# plooter_2.net
KiCad netlist of a schematic drawn in EAGLE
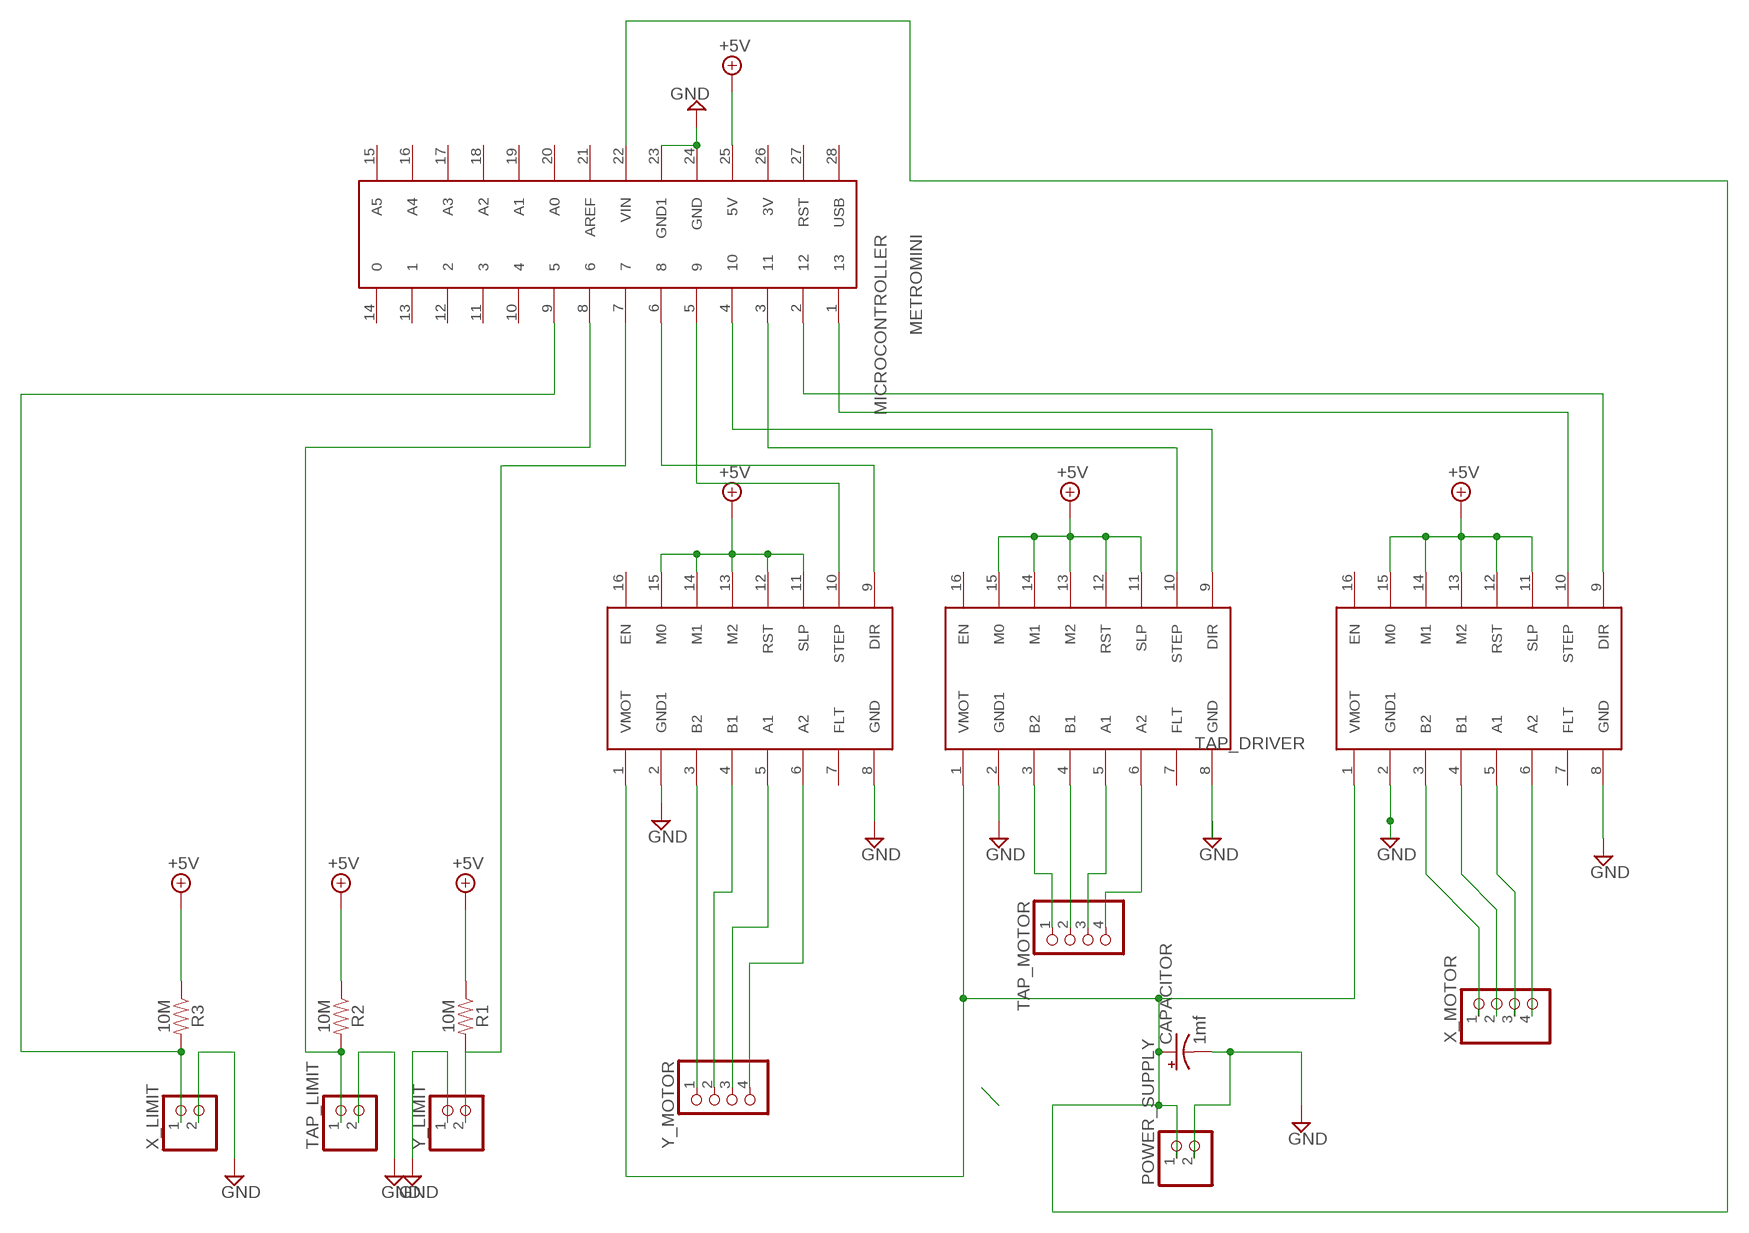
[diagram p0: schematic, sheet 1]

(export (version "E")
  (design (tool "Eeschema 10.0.6"))
  (components
    (comp (ref "CAPACITOR")
      (value "1mf")
      (footprint "eagle-import:CPOL-RADIAL-5MM-10MM-KIT")
      (libsource (lib "eagle-import") (part "1000UF-RADIAL-5MM-35V-20%-KIT"))
    )
    (comp (ref "MICROCONTROLLER")
      (value "METROMINI")
      (footprint "eagle-import:METROMINI")
      (libsource (lib "eagle-import") (part "METROMINI"))
    )
    (comp (ref "POWER_SUPPLY")
      (value "PINHD-1X2")
      (footprint "eagle-import:1X02")
      (libsource (lib "eagle-import") (part "PINHD-1X2"))
    )
    (comp (ref "R1")
      (value "10M")
      (footprint "eagle-import:AXIAL-0.3")
      (libsource (lib "eagle-import") (part "10MOHM-HORIZ-1/4W-5%"))
    )
    (comp (ref "R2")
      (value "10M")
      (footprint "eagle-import:AXIAL-0.3")
      (libsource (lib "eagle-import") (part "10MOHM-HORIZ-1/4W-5%"))
    )
    (comp (ref "R3")
      (value "10M")
      (footprint "eagle-import:AXIAL-0.3")
      (libsource (lib "eagle-import") (part "10MOHM-HORIZ-1/4W-5%"))
    )
    (comp (ref "TAP_DRIVER")
      (value "DRV8825")
      (footprint "eagle-import:DRV8825")
      (libsource (lib "eagle-import") (part "DRV8825"))
    )
    (comp (ref "TAP_LIMIT")
      (value "PINHD-1X2")
      (footprint "eagle-import:1X02")
      (libsource (lib "eagle-import") (part "PINHD-1X2"))
    )
    (comp (ref "TAP_MOTOR")
      (value "PINHD-1X4")
      (footprint "eagle-import:1X04")
      (libsource (lib "eagle-import") (part "PINHD-1X4"))
    )
    (comp (ref "X_DRIVER")
      (value "DRV8825")
      (footprint "eagle-import:DRV8825")
      (libsource (lib "eagle-import") (part "DRV8825"))
    )
    (comp (ref "X_LIMIT")
      (value "PINHD-1X2")
      (footprint "eagle-import:1X02")
      (libsource (lib "eagle-import") (part "PINHD-1X2"))
    )
    (comp (ref "X_MOTOR")
      (value "PINHD-1X4")
      (footprint "eagle-import:1X04")
      (libsource (lib "eagle-import") (part "PINHD-1X4"))
    )
    (comp (ref "Y_DRIVER")
      (value "DRV8825")
      (footprint "eagle-import:DRV8825")
      (libsource (lib "eagle-import") (part "DRV8825"))
    )
    (comp (ref "Y_LIMIT")
      (value "PINHD-1X2")
      (footprint "eagle-import:1X02")
      (libsource (lib "eagle-import") (part "PINHD-1X2"))
    )
    (comp (ref "Y_MOTOR")
      (value "PINHD-1X4")
      (footprint "eagle-import:1X04")
      (libsource (lib "eagle-import") (part "PINHD-1X4"))
    )
  )
  (nets
    (net (code "1") (name "+5V") (class "Default")
      (node (ref "MICROCONTROLLER") (pin "25") (pinfunction "5V_25") (pintype "bidirectional"))
      (node (ref "R1") (pin "P$1") (pinfunction "1_P$1") (pintype "passive"))
      (node (ref "R2") (pin "P$1") (pinfunction "1_P$1") (pintype "passive"))
      (node (ref "R3") (pin "P$1") (pinfunction "1_P$1") (pintype "passive"))
      (node (ref "TAP_DRIVER") (pin "11") (pinfunction "SLP_11") (pintype "bidirectional"))
      (node (ref "TAP_DRIVER") (pin "12") (pinfunction "RST_12") (pintype "bidirectional"))
      (node (ref "TAP_DRIVER") (pin "13") (pinfunction "M2_13") (pintype "bidirectional"))
      (node (ref "TAP_DRIVER") (pin "14") (pinfunction "M1_14") (pintype "bidirectional"))
      (node (ref "TAP_DRIVER") (pin "15") (pinfunction "M0_15") (pintype "bidirectional"))
      (node (ref "X_DRIVER") (pin "11") (pinfunction "SLP_11") (pintype "bidirectional"))
      (node (ref "X_DRIVER") (pin "12") (pinfunction "RST_12") (pintype "bidirectional"))
      (node (ref "X_DRIVER") (pin "13") (pinfunction "M2_13") (pintype "bidirectional"))
      (node (ref "X_DRIVER") (pin "14") (pinfunction "M1_14") (pintype "bidirectional"))
      (node (ref "X_DRIVER") (pin "15") (pinfunction "M0_15") (pintype "bidirectional"))
      (node (ref "Y_DRIVER") (pin "11") (pinfunction "SLP_11") (pintype "bidirectional"))
      (node (ref "Y_DRIVER") (pin "12") (pinfunction "RST_12") (pintype "bidirectional"))
      (node (ref "Y_DRIVER") (pin "13") (pinfunction "M2_13") (pintype "bidirectional"))
      (node (ref "Y_DRIVER") (pin "14") (pinfunction "M1_14") (pintype "bidirectional"))
      (node (ref "Y_DRIVER") (pin "15") (pinfunction "M0_15") (pintype "bidirectional"))
    )
    (net (code "2") (name "GND") (class "Default")
      (node (ref "CAPACITOR") (pin "-") (pinfunction "-_-") (pintype "passive"))
      (node (ref "MICROCONTROLLER") (pin "23") (pinfunction "GND1_23") (pintype "bidirectional"))
      (node (ref "MICROCONTROLLER") (pin "24") (pinfunction "GND_24") (pintype "bidirectional"))
      (node (ref "POWER_SUPPLY") (pin "2") (pinfunction "2_2") (pintype "passive"))
      (node (ref "TAP_DRIVER") (pin "2") (pinfunction "GND1_2") (pintype "bidirectional"))
      (node (ref "TAP_DRIVER") (pin "8") (pinfunction "GND_8") (pintype "bidirectional"))
      (node (ref "TAP_LIMIT") (pin "2") (pinfunction "2_2") (pintype "passive"))
      (node (ref "X_DRIVER") (pin "2") (pinfunction "GND1_2") (pintype "bidirectional"))
      (node (ref "X_DRIVER") (pin "8") (pinfunction "GND_8") (pintype "bidirectional"))
      (node (ref "X_LIMIT") (pin "2") (pinfunction "2_2") (pintype "passive"))
      (node (ref "Y_DRIVER") (pin "2") (pinfunction "GND1_2") (pintype "bidirectional"))
      (node (ref "Y_DRIVER") (pin "8") (pinfunction "GND_8") (pintype "bidirectional"))
      (node (ref "Y_LIMIT") (pin "1") (pinfunction "1_1") (pintype "passive"))
    )
    (net (code "3") (name "Net-(MICROCONTROLLER-5)") (class "Default")
      (node (ref "MICROCONTROLLER") (pin "9") (pinfunction "5_9") (pintype "bidirectional"))
      (node (ref "R3") (pin "P$2") (pinfunction "2_P$2") (pintype "passive"))
      (node (ref "X_LIMIT") (pin "1") (pinfunction "1_1") (pintype "passive"))
    )
    (net (code "4") (name "Net-(MICROCONTROLLER-6)") (class "Default")
      (node (ref "MICROCONTROLLER") (pin "8") (pinfunction "6_8") (pintype "bidirectional"))
      (node (ref "R2") (pin "P$2") (pinfunction "2_P$2") (pintype "passive"))
      (node (ref "TAP_LIMIT") (pin "1") (pinfunction "1_1") (pintype "passive"))
    )
    (net (code "5") (name "Net-(MICROCONTROLLER-8)") (class "Default")
      (node (ref "MICROCONTROLLER") (pin "6") (pinfunction "8_6") (pintype "bidirectional"))
      (node (ref "Y_DRIVER") (pin "9") (pinfunction "DIR_9") (pintype "bidirectional"))
    )
    (net (code "6") (name "Net-(MICROCONTROLLER-9)") (class "Default")
      (node (ref "MICROCONTROLLER") (pin "5") (pinfunction "9_5") (pintype "bidirectional"))
      (node (ref "Y_DRIVER") (pin "10") (pinfunction "STEP_10") (pintype "bidirectional"))
    )
    (net (code "7") (name "Net-(MICROCONTROLLER-10)") (class "Default")
      (node (ref "MICROCONTROLLER") (pin "4") (pinfunction "10_4") (pintype "bidirectional"))
      (node (ref "TAP_DRIVER") (pin "9") (pinfunction "DIR_9") (pintype "bidirectional"))
    )
    (net (code "8") (name "Net-(MICROCONTROLLER-11)") (class "Default")
      (node (ref "MICROCONTROLLER") (pin "3") (pinfunction "11_3") (pintype "bidirectional"))
      (node (ref "TAP_DRIVER") (pin "10") (pinfunction "STEP_10") (pintype "bidirectional"))
    )
    (net (code "9") (name "Net-(MICROCONTROLLER-12)") (class "Default")
      (node (ref "MICROCONTROLLER") (pin "2") (pinfunction "12_2") (pintype "bidirectional"))
      (node (ref "X_DRIVER") (pin "9") (pinfunction "DIR_9") (pintype "bidirectional"))
    )
    (net (code "10") (name "Net-(MICROCONTROLLER-13)") (class "Default")
      (node (ref "MICROCONTROLLER") (pin "1") (pinfunction "13_1") (pintype "bidirectional"))
      (node (ref "X_DRIVER") (pin "10") (pinfunction "STEP_10") (pintype "bidirectional"))
    )
    (net (code "11") (name "Net-(MICROCONTROLLER-VIN)") (class "Default")
      (node (ref "CAPACITOR") (pin "+") (pinfunction "+_+") (pintype "passive"))
      (node (ref "MICROCONTROLLER") (pin "22") (pinfunction "VIN_22") (pintype "bidirectional"))
      (node (ref "POWER_SUPPLY") (pin "1") (pinfunction "1_1") (pintype "passive"))
      (node (ref "TAP_DRIVER") (pin "1") (pinfunction "VMOT_1") (pintype "bidirectional"))
      (node (ref "X_DRIVER") (pin "1") (pinfunction "VMOT_1") (pintype "bidirectional"))
      (node (ref "Y_DRIVER") (pin "1") (pinfunction "VMOT_1") (pintype "bidirectional"))
    )
    (net (code "12") (name "Net-(R1-2)") (class "Default")
      (node (ref "MICROCONTROLLER") (pin "7") (pinfunction "7_7") (pintype "bidirectional"))
      (node (ref "R1") (pin "P$2") (pinfunction "2_P$2") (pintype "passive"))
      (node (ref "Y_LIMIT") (pin "2") (pinfunction "2_2") (pintype "passive"))
    )
    (net (code "13") (name "Net-(TAP_DRIVER-A1)") (class "Default")
      (node (ref "TAP_DRIVER") (pin "5") (pinfunction "A1_5") (pintype "bidirectional"))
      (node (ref "TAP_MOTOR") (pin "3") (pinfunction "3_3") (pintype "passive"))
    )
    (net (code "14") (name "Net-(TAP_DRIVER-A2)") (class "Default")
      (node (ref "TAP_DRIVER") (pin "6") (pinfunction "A2_6") (pintype "bidirectional"))
      (node (ref "TAP_MOTOR") (pin "4") (pinfunction "4_4") (pintype "passive"))
    )
    (net (code "15") (name "Net-(TAP_DRIVER-B1)") (class "Default")
      (node (ref "TAP_DRIVER") (pin "4") (pinfunction "B1_4") (pintype "bidirectional"))
      (node (ref "TAP_MOTOR") (pin "2") (pinfunction "2_2") (pintype "passive"))
    )
    (net (code "16") (name "Net-(TAP_DRIVER-B2)") (class "Default")
      (node (ref "TAP_DRIVER") (pin "3") (pinfunction "B2_3") (pintype "bidirectional"))
      (node (ref "TAP_MOTOR") (pin "1") (pinfunction "1_1") (pintype "passive"))
    )
    (net (code "17") (name "Net-(X_DRIVER-A1)") (class "Default")
      (node (ref "X_DRIVER") (pin "5") (pinfunction "A1_5") (pintype "bidirectional"))
      (node (ref "X_MOTOR") (pin "3") (pinfunction "3_3") (pintype "passive"))
    )
    (net (code "18") (name "Net-(X_DRIVER-A2)") (class "Default")
      (node (ref "X_DRIVER") (pin "6") (pinfunction "A2_6") (pintype "bidirectional"))
      (node (ref "X_MOTOR") (pin "4") (pinfunction "4_4") (pintype "passive"))
    )
    (net (code "19") (name "Net-(X_DRIVER-B1)") (class "Default")
      (node (ref "X_DRIVER") (pin "4") (pinfunction "B1_4") (pintype "bidirectional"))
      (node (ref "X_MOTOR") (pin "2") (pinfunction "2_2") (pintype "passive"))
    )
    (net (code "20") (name "Net-(X_DRIVER-B2)") (class "Default")
      (node (ref "X_DRIVER") (pin "3") (pinfunction "B2_3") (pintype "bidirectional"))
      (node (ref "X_MOTOR") (pin "1") (pinfunction "1_1") (pintype "passive"))
    )
    (net (code "21") (name "Net-(Y_DRIVER-A1)") (class "Default")
      (node (ref "Y_DRIVER") (pin "5") (pinfunction "A1_5") (pintype "bidirectional"))
      (node (ref "Y_MOTOR") (pin "3") (pinfunction "3_3") (pintype "passive"))
    )
    (net (code "22") (name "Net-(Y_DRIVER-A2)") (class "Default")
      (node (ref "Y_DRIVER") (pin "6") (pinfunction "A2_6") (pintype "bidirectional"))
      (node (ref "Y_MOTOR") (pin "4") (pinfunction "4_4") (pintype "passive"))
    )
    (net (code "23") (name "Net-(Y_DRIVER-B1)") (class "Default")
      (node (ref "Y_DRIVER") (pin "4") (pinfunction "B1_4") (pintype "bidirectional"))
      (node (ref "Y_MOTOR") (pin "2") (pinfunction "2_2") (pintype "passive"))
    )
    (net (code "24") (name "Net-(Y_DRIVER-B2)") (class "Default")
      (node (ref "Y_DRIVER") (pin "3") (pinfunction "B2_3") (pintype "bidirectional"))
      (node (ref "Y_MOTOR") (pin "1") (pinfunction "1_1") (pintype "passive"))
    )
    (net (code "25") (name "unconnected-(MICROCONTROLLER-0-Pad14)") (class "Default")
      (node (ref "MICROCONTROLLER") (pin "14") (pinfunction "0_14") (pintype "bidirectional"))
    )
    (net (code "26") (name "unconnected-(MICROCONTROLLER-1-Pad13)") (class "Default")
      (node (ref "MICROCONTROLLER") (pin "13") (pinfunction "1_13") (pintype "bidirectional"))
    )
    (net (code "27") (name "unconnected-(MICROCONTROLLER-2-Pad12)") (class "Default")
      (node (ref "MICROCONTROLLER") (pin "12") (pinfunction "2_12") (pintype "bidirectional"))
    )
    (net (code "28") (name "unconnected-(MICROCONTROLLER-3-Pad11)") (class "Default")
      (node (ref "MICROCONTROLLER") (pin "11") (pinfunction "3_11") (pintype "bidirectional"))
    )
    (net (code "29") (name "unconnected-(MICROCONTROLLER-3V-Pad26)") (class "Default")
      (node (ref "MICROCONTROLLER") (pin "26") (pinfunction "3V_26") (pintype "bidirectional"))
    )
    (net (code "30") (name "unconnected-(MICROCONTROLLER-4-Pad10)") (class "Default")
      (node (ref "MICROCONTROLLER") (pin "10") (pinfunction "4_10") (pintype "bidirectional"))
    )
    (net (code "31") (name "unconnected-(MICROCONTROLLER-A0-Pad20)") (class "Default")
      (node (ref "MICROCONTROLLER") (pin "20") (pinfunction "A0_20") (pintype "bidirectional"))
    )
    (net (code "32") (name "unconnected-(MICROCONTROLLER-A1-Pad19)") (class "Default")
      (node (ref "MICROCONTROLLER") (pin "19") (pinfunction "A1_19") (pintype "bidirectional"))
    )
    (net (code "33") (name "unconnected-(MICROCONTROLLER-A2-Pad18)") (class "Default")
      (node (ref "MICROCONTROLLER") (pin "18") (pinfunction "A2_18") (pintype "bidirectional"))
    )
    (net (code "34") (name "unconnected-(MICROCONTROLLER-A3-Pad17)") (class "Default")
      (node (ref "MICROCONTROLLER") (pin "17") (pinfunction "A3_17") (pintype "bidirectional"))
    )
    (net (code "35") (name "unconnected-(MICROCONTROLLER-A4-Pad16)") (class "Default")
      (node (ref "MICROCONTROLLER") (pin "16") (pinfunction "A4_16") (pintype "bidirectional"))
    )
    (net (code "36") (name "unconnected-(MICROCONTROLLER-A5-Pad15)") (class "Default")
      (node (ref "MICROCONTROLLER") (pin "15") (pinfunction "A5_15") (pintype "bidirectional"))
    )
    (net (code "37") (name "unconnected-(MICROCONTROLLER-AREF-Pad21)") (class "Default")
      (node (ref "MICROCONTROLLER") (pin "21") (pinfunction "AREF_21") (pintype "bidirectional"))
    )
    (net (code "38") (name "unconnected-(MICROCONTROLLER-RST-Pad27)") (class "Default")
      (node (ref "MICROCONTROLLER") (pin "27") (pinfunction "RST_27") (pintype "bidirectional"))
    )
    (net (code "39") (name "unconnected-(MICROCONTROLLER-USB-Pad28)") (class "Default")
      (node (ref "MICROCONTROLLER") (pin "28") (pinfunction "USB_28") (pintype "bidirectional"))
    )
    (net (code "40") (name "unconnected-(TAP_DRIVER-EN-Pad16)") (class "Default")
      (node (ref "TAP_DRIVER") (pin "16") (pinfunction "EN_16") (pintype "bidirectional"))
    )
    (net (code "41") (name "unconnected-(TAP_DRIVER-FLT-Pad7)") (class "Default")
      (node (ref "TAP_DRIVER") (pin "7") (pinfunction "FLT_7") (pintype "bidirectional"))
    )
    (net (code "42") (name "unconnected-(X_DRIVER-EN-Pad16)") (class "Default")
      (node (ref "X_DRIVER") (pin "16") (pinfunction "EN_16") (pintype "bidirectional"))
    )
    (net (code "43") (name "unconnected-(X_DRIVER-FLT-Pad7)") (class "Default")
      (node (ref "X_DRIVER") (pin "7") (pinfunction "FLT_7") (pintype "bidirectional"))
    )
    (net (code "44") (name "unconnected-(Y_DRIVER-EN-Pad16)") (class "Default")
      (node (ref "Y_DRIVER") (pin "16") (pinfunction "EN_16") (pintype "bidirectional"))
    )
    (net (code "45") (name "unconnected-(Y_DRIVER-FLT-Pad7)") (class "Default")
      (node (ref "Y_DRIVER") (pin "7") (pinfunction "FLT_7") (pintype "bidirectional"))
    )
  )
)
